# ProProject_Microplate-Reader-V1_0_2024-0.net
KiCad netlist of a schematic drawn in EasyEDA Pro
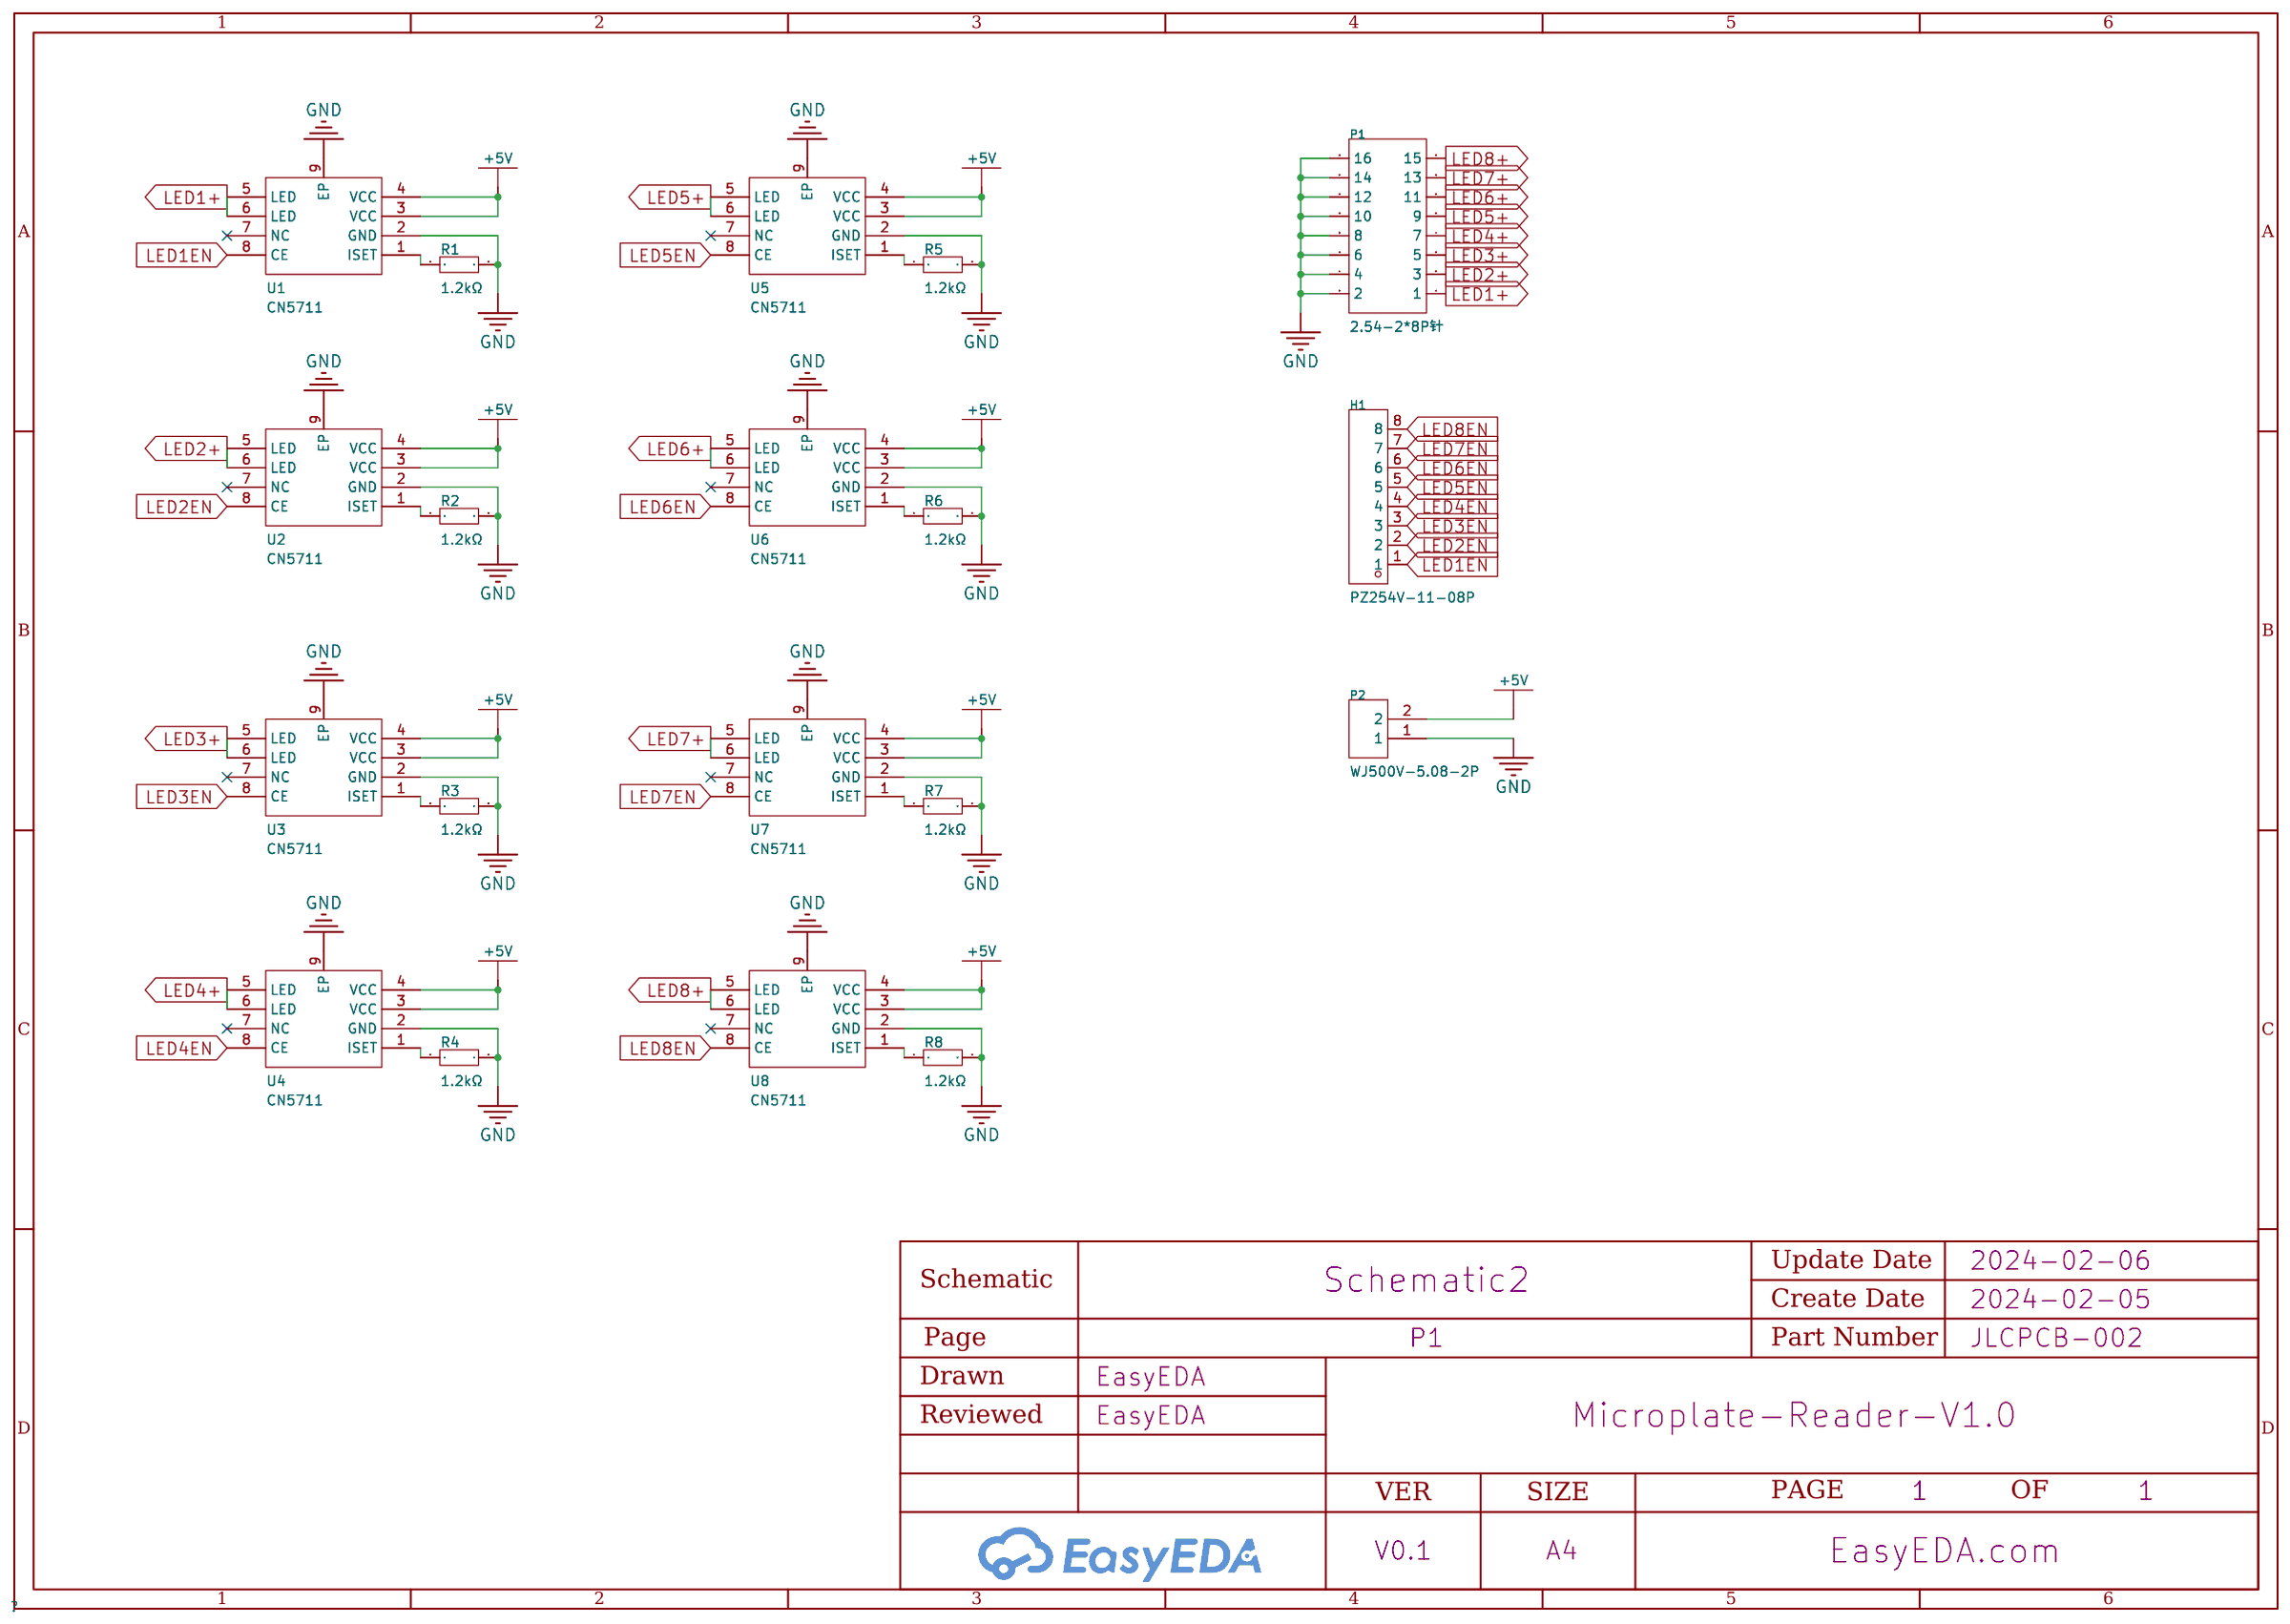
[diagram p0: schematic sheet]

(export (version "E")
  (design (tool "Eeschema 10.0.6"))
  (components
    (comp (ref "H1")
      (value "PZ254V-11-08P")
      (footprint "easyedapro:HDR-TH_8P-P2.54-V-M")
      (fields (field (name "Manufacturer") "XFCN(兴飞)"))
      (libsource (lib "easyedapro") (part "PZ254V-11-08P"))
    )
    (comp (ref "P1")
      (value "2.54-2*8P针")
      (footprint "easyedapro:HDR-TH_16P-P2.54-V-M-R2-C8-S2.54")
      (fields (field (name "Manufacturer") "BOOMELE(博穆精密)"))
      (libsource (lib "easyedapro") (part "Header-Male-2.54_2x8"))
    )
    (comp (ref "P2")
      (value "WJ500V-5.08-2P")
      (footprint "easyedapro:CONN-TH_2P-P5.00_WJ500V-5.08-2P")
      (fields (field (name "Manufacturer") "KANGNEX(康奈克斯电气)"))
      (libsource (lib "easyedapro") (part "WJ500V-5.08-2P-14-00A"))
    )
    (comp (ref "R1")
      (value "1.2kΩ")
      (footprint "easyedapro:R0603")
      (fields
        (field (name "Manufacturer Part") "CR0603J1K20P05Z")
        (field (name "Manufacturer") "EVER OHMS(天二科技)")
      )
      (libsource (lib "easyedapro") (part "Res"))
    )
    (comp (ref "R2")
      (value "1.2kΩ")
      (footprint "easyedapro:R0603")
      (fields
        (field (name "Manufacturer Part") "CR0603J1K20P05Z")
        (field (name "Manufacturer") "EVER OHMS(天二科技)")
      )
      (libsource (lib "easyedapro") (part "Res"))
    )
    (comp (ref "R3")
      (value "1.2kΩ")
      (footprint "easyedapro:R0603")
      (fields
        (field (name "Manufacturer Part") "CR0603J1K20P05Z")
        (field (name "Manufacturer") "EVER OHMS(天二科技)")
      )
      (libsource (lib "easyedapro") (part "Res"))
    )
    (comp (ref "R4")
      (value "1.2kΩ")
      (footprint "easyedapro:R0603")
      (fields
        (field (name "Manufacturer Part") "CR0603J1K20P05Z")
        (field (name "Manufacturer") "EVER OHMS(天二科技)")
      )
      (libsource (lib "easyedapro") (part "Res"))
    )
    (comp (ref "R5")
      (value "1.2kΩ")
      (footprint "easyedapro:R0603")
      (fields
        (field (name "Manufacturer Part") "CR0603J1K20P05Z")
        (field (name "Manufacturer") "EVER OHMS(天二科技)")
      )
      (libsource (lib "easyedapro") (part "Res"))
    )
    (comp (ref "R6")
      (value "1.2kΩ")
      (footprint "easyedapro:R0603")
      (fields
        (field (name "Manufacturer Part") "CR0603J1K20P05Z")
        (field (name "Manufacturer") "EVER OHMS(天二科技)")
      )
      (libsource (lib "easyedapro") (part "Res"))
    )
    (comp (ref "R7")
      (value "1.2kΩ")
      (footprint "easyedapro:R0603")
      (fields
        (field (name "Manufacturer Part") "CR0603J1K20P05Z")
        (field (name "Manufacturer") "EVER OHMS(天二科技)")
      )
      (libsource (lib "easyedapro") (part "Res"))
    )
    (comp (ref "R8")
      (value "1.2kΩ")
      (footprint "easyedapro:R0603")
      (fields
        (field (name "Manufacturer Part") "CR0603J1K20P05Z")
        (field (name "Manufacturer") "EVER OHMS(天二科技)")
      )
      (libsource (lib "easyedapro") (part "Res"))
    )
    (comp (ref "U1")
      (value "CN5711")
      (footprint "easyedapro:SOIC-8_L5.0-W4.0-P1.27-LS6.0-BL-EP2.0")
      (fields (field (name "Manufacturer") "CONSONANCE(上海如韵)"))
      (libsource (lib "easyedapro") (part "CN5711"))
    )
    (comp (ref "U2")
      (value "CN5711")
      (footprint "easyedapro:SOIC-8_L5.0-W4.0-P1.27-LS6.0-BL-EP2.0")
      (fields (field (name "Manufacturer") "CONSONANCE(上海如韵)"))
      (libsource (lib "easyedapro") (part "CN5711"))
    )
    (comp (ref "U3")
      (value "CN5711")
      (footprint "easyedapro:SOIC-8_L5.0-W4.0-P1.27-LS6.0-BL-EP2.0")
      (fields (field (name "Manufacturer") "CONSONANCE(上海如韵)"))
      (libsource (lib "easyedapro") (part "CN5711"))
    )
    (comp (ref "U4")
      (value "CN5711")
      (footprint "easyedapro:SOIC-8_L5.0-W4.0-P1.27-LS6.0-BL-EP2.0")
      (fields (field (name "Manufacturer") "CONSONANCE(上海如韵)"))
      (libsource (lib "easyedapro") (part "CN5711"))
    )
    (comp (ref "U5")
      (value "CN5711")
      (footprint "easyedapro:SOIC-8_L5.0-W4.0-P1.27-LS6.0-BL-EP2.0")
      (fields (field (name "Manufacturer") "CONSONANCE(上海如韵)"))
      (libsource (lib "easyedapro") (part "CN5711"))
    )
    (comp (ref "U6")
      (value "CN5711")
      (footprint "easyedapro:SOIC-8_L5.0-W4.0-P1.27-LS6.0-BL-EP2.0")
      (fields (field (name "Manufacturer") "CONSONANCE(上海如韵)"))
      (libsource (lib "easyedapro") (part "CN5711"))
    )
    (comp (ref "U7")
      (value "CN5711")
      (footprint "easyedapro:SOIC-8_L5.0-W4.0-P1.27-LS6.0-BL-EP2.0")
      (fields (field (name "Manufacturer") "CONSONANCE(上海如韵)"))
      (libsource (lib "easyedapro") (part "CN5711"))
    )
    (comp (ref "U8")
      (value "CN5711")
      (footprint "easyedapro:SOIC-8_L5.0-W4.0-P1.27-LS6.0-BL-EP2.0")
      (fields (field (name "Manufacturer") "CONSONANCE(上海如韵)"))
      (libsource (lib "easyedapro") (part "CN5711"))
    )
  )
  (nets
    (net (code "1") (name "+5V") (class "Default")
      (node (ref "P2") (pin "2") (pinfunction "2_2") (pintype "input"))
      (node (ref "U1") (pin "3") (pinfunction "VCC_3") (pintype "input"))
      (node (ref "U1") (pin "4") (pinfunction "VCC_4") (pintype "input"))
      (node (ref "U2") (pin "3") (pinfunction "VCC_3") (pintype "input"))
      (node (ref "U2") (pin "4") (pinfunction "VCC_4") (pintype "input"))
      (node (ref "U3") (pin "3") (pinfunction "VCC_3") (pintype "input"))
      (node (ref "U3") (pin "4") (pinfunction "VCC_4") (pintype "input"))
      (node (ref "U4") (pin "3") (pinfunction "VCC_3") (pintype "input"))
      (node (ref "U4") (pin "4") (pinfunction "VCC_4") (pintype "input"))
      (node (ref "U5") (pin "3") (pinfunction "VCC_3") (pintype "input"))
      (node (ref "U5") (pin "4") (pinfunction "VCC_4") (pintype "input"))
      (node (ref "U6") (pin "3") (pinfunction "VCC_3") (pintype "input"))
      (node (ref "U6") (pin "4") (pinfunction "VCC_4") (pintype "input"))
      (node (ref "U7") (pin "3") (pinfunction "VCC_3") (pintype "input"))
      (node (ref "U7") (pin "4") (pinfunction "VCC_4") (pintype "input"))
      (node (ref "U8") (pin "3") (pinfunction "VCC_3") (pintype "input"))
      (node (ref "U8") (pin "4") (pinfunction "VCC_4") (pintype "input"))
    )
    (net (code "2") (name "GND") (class "Default")
      (node (ref "P1") (pin "10") (pinfunction "10_10") (pintype "input"))
      (node (ref "P1") (pin "12") (pinfunction "12_12") (pintype "input"))
      (node (ref "P1") (pin "14") (pinfunction "14_14") (pintype "input"))
      (node (ref "P1") (pin "16") (pinfunction "16_16") (pintype "input"))
      (node (ref "P1") (pin "2") (pinfunction "2_2") (pintype "input"))
      (node (ref "P1") (pin "4") (pinfunction "4_4") (pintype "input"))
      (node (ref "P1") (pin "6") (pinfunction "6_6") (pintype "input"))
      (node (ref "P1") (pin "8") (pinfunction "8_8") (pintype "input"))
      (node (ref "P2") (pin "1") (pinfunction "1_1") (pintype "input"))
      (node (ref "R1") (pin "2") (pinfunction "2_2") (pintype "input"))
      (node (ref "R2") (pin "2") (pinfunction "2_2") (pintype "input"))
      (node (ref "R3") (pin "2") (pinfunction "2_2") (pintype "input"))
      (node (ref "R4") (pin "2") (pinfunction "2_2") (pintype "input"))
      (node (ref "R5") (pin "2") (pinfunction "2_2") (pintype "input"))
      (node (ref "R6") (pin "2") (pinfunction "2_2") (pintype "input"))
      (node (ref "R7") (pin "2") (pinfunction "2_2") (pintype "input"))
      (node (ref "R8") (pin "2") (pinfunction "2_2") (pintype "input"))
      (node (ref "U1") (pin "2") (pinfunction "GND_2") (pintype "input"))
      (node (ref "U1") (pin "9") (pinfunction "EP_9") (pintype "input"))
      (node (ref "U2") (pin "2") (pinfunction "GND_2") (pintype "input"))
      (node (ref "U2") (pin "9") (pinfunction "EP_9") (pintype "input"))
      (node (ref "U3") (pin "2") (pinfunction "GND_2") (pintype "input"))
      (node (ref "U3") (pin "9") (pinfunction "EP_9") (pintype "input"))
      (node (ref "U4") (pin "2") (pinfunction "GND_2") (pintype "input"))
      (node (ref "U4") (pin "9") (pinfunction "EP_9") (pintype "input"))
      (node (ref "U5") (pin "2") (pinfunction "GND_2") (pintype "input"))
      (node (ref "U5") (pin "9") (pinfunction "EP_9") (pintype "input"))
      (node (ref "U6") (pin "2") (pinfunction "GND_2") (pintype "input"))
      (node (ref "U6") (pin "9") (pinfunction "EP_9") (pintype "input"))
      (node (ref "U7") (pin "2") (pinfunction "GND_2") (pintype "input"))
      (node (ref "U7") (pin "9") (pinfunction "EP_9") (pintype "input"))
      (node (ref "U8") (pin "2") (pinfunction "GND_2") (pintype "input"))
      (node (ref "U8") (pin "9") (pinfunction "EP_9") (pintype "input"))
    )
    (net (code "3") (name "LED1+") (class "Default")
      (node (ref "P1") (pin "1") (pinfunction "1_1") (pintype "input"))
      (node (ref "U1") (pin "5") (pinfunction "LED_5") (pintype "input"))
      (node (ref "U1") (pin "6") (pinfunction "LED_6") (pintype "input"))
    )
    (net (code "4") (name "LED1EN") (class "Default")
      (node (ref "H1") (pin "1") (pinfunction "1_1") (pintype "input"))
      (node (ref "U1") (pin "8") (pinfunction "CE_8") (pintype "input"))
    )
    (net (code "5") (name "LED2+") (class "Default")
      (node (ref "P1") (pin "3") (pinfunction "3_3") (pintype "input"))
      (node (ref "U2") (pin "5") (pinfunction "LED_5") (pintype "input"))
      (node (ref "U2") (pin "6") (pinfunction "LED_6") (pintype "input"))
    )
    (net (code "6") (name "LED2EN") (class "Default")
      (node (ref "H1") (pin "2") (pinfunction "2_2") (pintype "input"))
      (node (ref "U2") (pin "8") (pinfunction "CE_8") (pintype "input"))
    )
    (net (code "7") (name "LED3+") (class "Default")
      (node (ref "P1") (pin "5") (pinfunction "5_5") (pintype "input"))
      (node (ref "U3") (pin "5") (pinfunction "LED_5") (pintype "input"))
      (node (ref "U3") (pin "6") (pinfunction "LED_6") (pintype "input"))
    )
    (net (code "8") (name "LED3EN") (class "Default")
      (node (ref "H1") (pin "3") (pinfunction "3_3") (pintype "input"))
      (node (ref "U3") (pin "8") (pinfunction "CE_8") (pintype "input"))
    )
    (net (code "9") (name "LED4+") (class "Default")
      (node (ref "P1") (pin "7") (pinfunction "7_7") (pintype "input"))
      (node (ref "U4") (pin "5") (pinfunction "LED_5") (pintype "input"))
      (node (ref "U4") (pin "6") (pinfunction "LED_6") (pintype "input"))
    )
    (net (code "10") (name "LED4EN") (class "Default")
      (node (ref "H1") (pin "4") (pinfunction "4_4") (pintype "input"))
      (node (ref "U4") (pin "8") (pinfunction "CE_8") (pintype "input"))
    )
    (net (code "11") (name "LED5+") (class "Default")
      (node (ref "P1") (pin "9") (pinfunction "9_9") (pintype "input"))
      (node (ref "U5") (pin "5") (pinfunction "LED_5") (pintype "input"))
      (node (ref "U5") (pin "6") (pinfunction "LED_6") (pintype "input"))
    )
    (net (code "12") (name "LED5EN") (class "Default")
      (node (ref "H1") (pin "5") (pinfunction "5_5") (pintype "input"))
      (node (ref "U5") (pin "8") (pinfunction "CE_8") (pintype "input"))
    )
    (net (code "13") (name "LED6+") (class "Default")
      (node (ref "P1") (pin "11") (pinfunction "11_11") (pintype "input"))
      (node (ref "U6") (pin "5") (pinfunction "LED_5") (pintype "input"))
      (node (ref "U6") (pin "6") (pinfunction "LED_6") (pintype "input"))
    )
    (net (code "14") (name "LED6EN") (class "Default")
      (node (ref "H1") (pin "6") (pinfunction "6_6") (pintype "input"))
      (node (ref "U6") (pin "8") (pinfunction "CE_8") (pintype "input"))
    )
    (net (code "15") (name "LED7+") (class "Default")
      (node (ref "P1") (pin "13") (pinfunction "13_13") (pintype "input"))
      (node (ref "U7") (pin "5") (pinfunction "LED_5") (pintype "input"))
      (node (ref "U7") (pin "6") (pinfunction "LED_6") (pintype "input"))
    )
    (net (code "16") (name "LED7EN") (class "Default")
      (node (ref "H1") (pin "7") (pinfunction "7_7") (pintype "input"))
      (node (ref "U7") (pin "8") (pinfunction "CE_8") (pintype "input"))
    )
    (net (code "17") (name "LED8+") (class "Default")
      (node (ref "P1") (pin "15") (pinfunction "15_15") (pintype "input"))
      (node (ref "U8") (pin "5") (pinfunction "LED_5") (pintype "input"))
      (node (ref "U8") (pin "6") (pinfunction "LED_6") (pintype "input"))
    )
    (net (code "18") (name "LED8EN") (class "Default")
      (node (ref "H1") (pin "8") (pinfunction "8_8") (pintype "input"))
      (node (ref "U8") (pin "8") (pinfunction "CE_8") (pintype "input"))
    )
    (net (code "19") (name "Net-(U1-ISET)") (class "Default")
      (node (ref "R1") (pin "1") (pinfunction "1_1") (pintype "input"))
      (node (ref "U1") (pin "1") (pinfunction "ISET_1") (pintype "input"))
    )
    (net (code "20") (name "Net-(U2-ISET)") (class "Default")
      (node (ref "R2") (pin "1") (pinfunction "1_1") (pintype "input"))
      (node (ref "U2") (pin "1") (pinfunction "ISET_1") (pintype "input"))
    )
    (net (code "21") (name "Net-(U3-ISET)") (class "Default")
      (node (ref "R3") (pin "1") (pinfunction "1_1") (pintype "input"))
      (node (ref "U3") (pin "1") (pinfunction "ISET_1") (pintype "input"))
    )
    (net (code "22") (name "Net-(U4-ISET)") (class "Default")
      (node (ref "R4") (pin "1") (pinfunction "1_1") (pintype "input"))
      (node (ref "U4") (pin "1") (pinfunction "ISET_1") (pintype "input"))
    )
    (net (code "23") (name "Net-(U5-ISET)") (class "Default")
      (node (ref "R5") (pin "1") (pinfunction "1_1") (pintype "input"))
      (node (ref "U5") (pin "1") (pinfunction "ISET_1") (pintype "input"))
    )
    (net (code "24") (name "Net-(U6-ISET)") (class "Default")
      (node (ref "R6") (pin "1") (pinfunction "1_1") (pintype "input"))
      (node (ref "U6") (pin "1") (pinfunction "ISET_1") (pintype "input"))
    )
    (net (code "25") (name "Net-(U7-ISET)") (class "Default")
      (node (ref "R7") (pin "1") (pinfunction "1_1") (pintype "input"))
      (node (ref "U7") (pin "1") (pinfunction "ISET_1") (pintype "input"))
    )
    (net (code "26") (name "Net-(U8-ISET)") (class "Default")
      (node (ref "R8") (pin "1") (pinfunction "1_1") (pintype "input"))
      (node (ref "U8") (pin "1") (pinfunction "ISET_1") (pintype "input"))
    )
    (net (code "27") (name "unconnected-(U1-NC-Pad7)") (class "Default")
      (node (ref "U1") (pin "7") (pinfunction "NC_7") (pintype "input+no_connect"))
    )
    (net (code "28") (name "unconnected-(U2-NC-Pad7)") (class "Default")
      (node (ref "U2") (pin "7") (pinfunction "NC_7") (pintype "input+no_connect"))
    )
    (net (code "29") (name "unconnected-(U3-NC-Pad7)") (class "Default")
      (node (ref "U3") (pin "7") (pinfunction "NC_7") (pintype "input+no_connect"))
    )
    (net (code "30") (name "unconnected-(U4-NC-Pad7)") (class "Default")
      (node (ref "U4") (pin "7") (pinfunction "NC_7") (pintype "input+no_connect"))
    )
    (net (code "31") (name "unconnected-(U5-NC-Pad7)") (class "Default")
      (node (ref "U5") (pin "7") (pinfunction "NC_7") (pintype "input+no_connect"))
    )
    (net (code "32") (name "unconnected-(U6-NC-Pad7)") (class "Default")
      (node (ref "U6") (pin "7") (pinfunction "NC_7") (pintype "input+no_connect"))
    )
    (net (code "33") (name "unconnected-(U7-NC-Pad7)") (class "Default")
      (node (ref "U7") (pin "7") (pinfunction "NC_7") (pintype "input+no_connect"))
    )
    (net (code "34") (name "unconnected-(U8-NC-Pad7)") (class "Default")
      (node (ref "U8") (pin "7") (pinfunction "NC_7") (pintype "input+no_connect"))
    )
  )
)
